# Adafruit_Motor_Bonnet_Rev_A.net
KiCad netlist of a schematic drawn in EAGLE
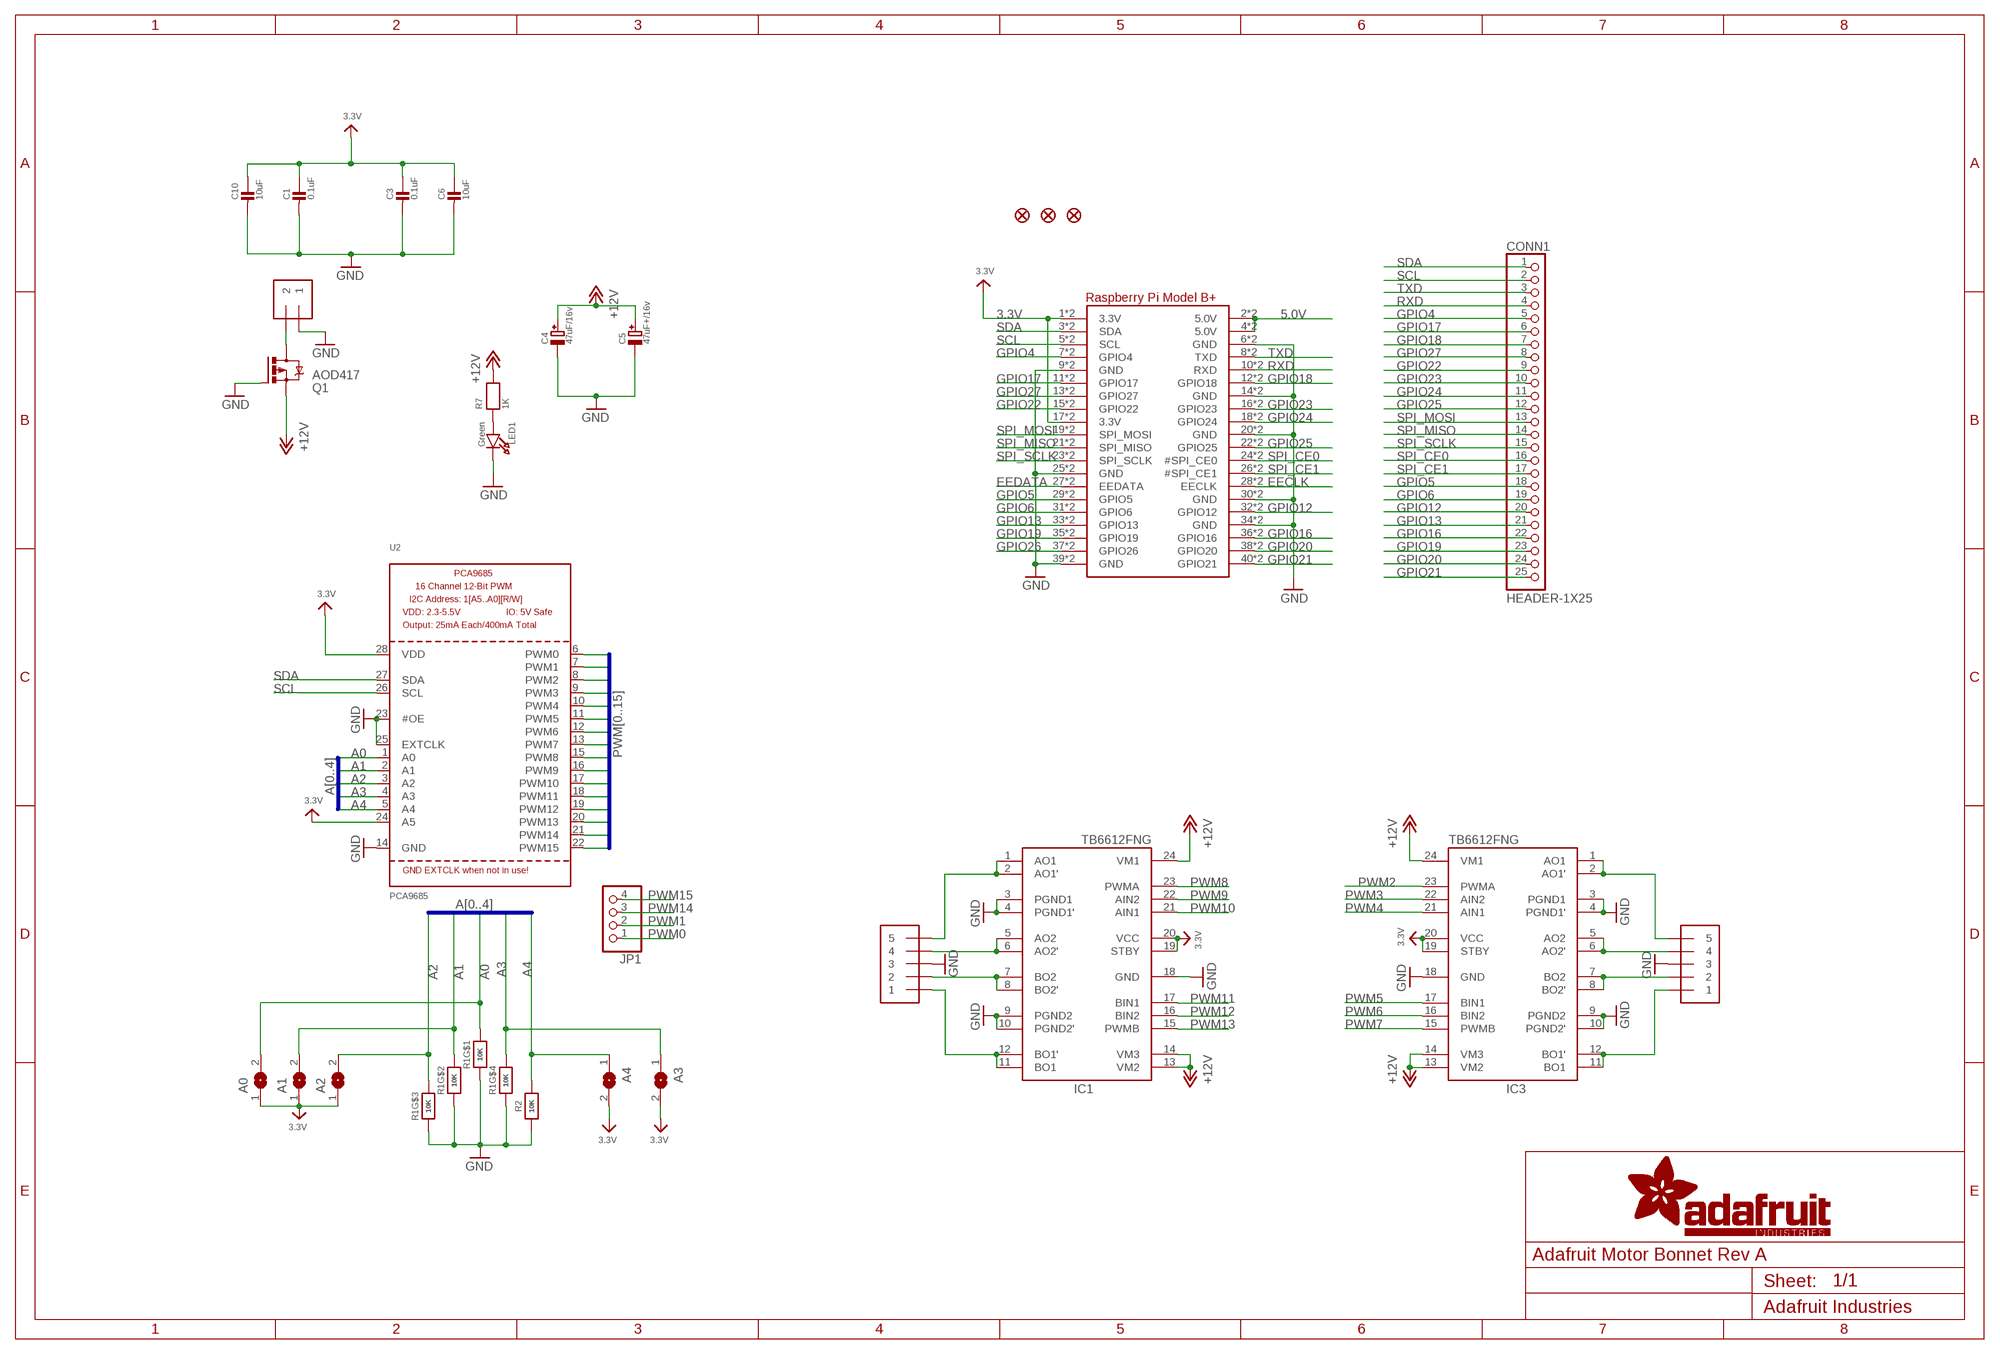
[diagram p0: schematic, sheet 1]

(export (version "E")
  (design (tool "Eeschema 10.0.6"))
  (components
    (comp (ref "A0")
      (value "SOLDERJUMPERREFLOW_NOPASTE")
      (footprint "eagle-import:SOLDERJUMPER_REFLOW_NOPASTE")
      (libsource (lib "eagle-import") (part "SOLDERJUMPERREFLOW_NOPASTE"))
    )
    (comp (ref "A1")
      (value "SOLDERJUMPERREFLOW_NOPASTE")
      (footprint "eagle-import:SOLDERJUMPER_REFLOW_NOPASTE")
      (libsource (lib "eagle-import") (part "SOLDERJUMPERREFLOW_NOPASTE"))
    )
    (comp (ref "A2")
      (value "SOLDERJUMPERREFLOW_NOPASTE")
      (footprint "eagle-import:SOLDERJUMPER_REFLOW_NOPASTE")
      (libsource (lib "eagle-import") (part "SOLDERJUMPERREFLOW_NOPASTE"))
    )
    (comp (ref "A3")
      (value "SOLDERJUMPERREFLOW_NOPASTE")
      (footprint "eagle-import:SOLDERJUMPER_REFLOW_NOPASTE")
      (libsource (lib "eagle-import") (part "SOLDERJUMPERREFLOW_NOPASTE"))
    )
    (comp (ref "A4")
      (value "SOLDERJUMPERREFLOW_NOPASTE")
      (footprint "eagle-import:SOLDERJUMPER_REFLOW_NOPASTE")
      (libsource (lib "eagle-import") (part "SOLDERJUMPERREFLOW_NOPASTE"))
    )
    (comp (ref "C1")
      (value "0.1uF")
      (footprint "eagle-import:0603-NO")
      (libsource (lib "eagle-import") (part "CAP_CERAMIC0603_NO"))
    )
    (comp (ref "C3")
      (value "0.1uF")
      (footprint "eagle-import:0603-NO")
      (libsource (lib "eagle-import") (part "CAP_CERAMIC0603_NO"))
    )
    (comp (ref "C4")
      (value "47uF/16v")
      (footprint "eagle-import:PANASONIC_C")
      (libsource (lib "eagle-import") (part "CAP_ELECTROLYTICPANASONIC_C"))
    )
    (comp (ref "C5")
      (value "47uF+/16v")
      (footprint "eagle-import:PANASONIC_C")
      (libsource (lib "eagle-import") (part "CAP_ELECTROLYTICPANASONIC_C"))
    )
    (comp (ref "C6")
      (value "10uF")
      (footprint "eagle-import:0805-NO")
      (libsource (lib "eagle-import") (part "CAP_CERAMIC0805-NOOUTLINE"))
    )
    (comp (ref "C10")
      (value "10uF")
      (footprint "eagle-import:0805-NO")
      (libsource (lib "eagle-import") (part "CAP_CERAMIC0805-NOOUTLINE"))
    )
    (comp (ref "CONN1")
      (value "HEADER-1X25")
      (footprint "eagle-import:1X25_ROUND_70MIL")
      (libsource (lib "eagle-import") (part "HEADER-1X25"))
    )
    (comp (ref "FID1")
      (value "FIDUCIAL_1MM")
      (footprint "eagle-import:FIDUCIAL_1MM")
      (libsource (lib "eagle-import") (part "FIDUCIAL_1MM"))
    )
    (comp (ref "FID2")
      (value "FIDUCIAL_1MM")
      (footprint "eagle-import:FIDUCIAL_1MM")
      (libsource (lib "eagle-import") (part "FIDUCIAL_1MM"))
    )
    (comp (ref "FID3")
      (value "FIDUCIAL_1MM")
      (footprint "eagle-import:FIDUCIAL_1MM")
      (libsource (lib "eagle-import") (part "FIDUCIAL_1MM"))
    )
    (comp (ref "IC1")
      (value "TB6612FNG")
      (footprint "eagle-import:SSOP24")
      (libsource (lib "eagle-import") (part "TB6612FNG"))
    )
    (comp (ref "IC3")
      (value "TB6612FNG")
      (footprint "eagle-import:SSOP24")
      (libsource (lib "eagle-import") (part "TB6612FNG"))
    )
    (comp (ref "J1")
      (value "1X5")
      (footprint "eagle-import:1X05-3.5MM")
      (libsource (lib "eagle-import") (part "1X5"))
    )
    (comp (ref "J3")
      (value "1X5")
      (footprint "eagle-import:1X05-3.5MM")
      (libsource (lib "eagle-import") (part "1X5"))
    )
    (comp (ref "JP1")
      (value "HEADER-1X4ROUND")
      (footprint "eagle-import:1X04_ROUND")
      (libsource (lib "eagle-import") (part "HEADER-1X4ROUND"))
    )
    (comp (ref "LED1")
      (value "Green")
      (footprint "eagle-import:CHIPLED_0805_NOOUTLINE")
      (libsource (lib "eagle-import") (part "LED0805_NOOUTLINE"))
    )
    (comp (ref "MPOWER")
      (value "1X2-3.5MM")
      (footprint "eagle-import:1X2-3.5MM")
      (libsource (lib "eagle-import") (part "1X2-3.5MM"))
    )
    (comp (ref "Q1")
      (value "AOD417")
      (footprint "eagle-import:D-PAK_TO252AA")
      (libsource (lib "eagle-import") (part "IRF?5305R"))
    )
    (comp (ref "R1")
      (value "10K")
      (footprint "eagle-import:RESPACK_4X0603")
      (libsource (lib "eagle-import") (part "RESISTOR_4PACK"))
    )
    (comp (ref "R2")
      (value "10K")
      (footprint "eagle-import:0603-NO")
      (libsource (lib "eagle-import") (part "RESISTOR_0603_NOOUT"))
    )
    (comp (ref "R7")
      (value "1K")
      (footprint "eagle-import:0603-NO")
      (libsource (lib "eagle-import") (part "RESISTOR_0603_NOOUT"))
    )
    (comp (ref "RPI1")
      (value "RASPBERRYPI_BPLUS_BONNET_THMSMT")
      (footprint "eagle-import:PI_BONNET_THMSMT")
      (libsource (lib "eagle-import") (part "RASPBERRYPI_BPLUS_BONNET_THMSMT"))
    )
    (comp (ref "U2")
      (value "PCA9685")
      (footprint "eagle-import:TSSOP28")
      (libsource (lib "eagle-import") (part "PCA9685"))
    )
  )
  (nets
    (net (code "1") (name "+12V") (class "Default")
      (node (ref "C4") (pin "+") (pinfunction "+_+") (pintype "passive"))
      (node (ref "C5") (pin "+") (pinfunction "+_+") (pintype "passive"))
      (node (ref "IC1") (pin "13") (pinfunction "VM2_13") (pintype "power_in"))
      (node (ref "IC1") (pin "14") (pinfunction "VM3_14") (pintype "power_in"))
      (node (ref "IC1") (pin "24") (pinfunction "VM1_24") (pintype "power_in"))
      (node (ref "IC3") (pin "13") (pinfunction "VM2_13") (pintype "power_in"))
      (node (ref "IC3") (pin "14") (pinfunction "VM3_14") (pintype "power_in"))
      (node (ref "IC3") (pin "24") (pinfunction "VM1_24") (pintype "power_in"))
      (node (ref "Q1") (pin "3") (pinfunction "S_3") (pintype "passive"))
      (node (ref "R7") (pin "2") (pinfunction "2_2") (pintype "passive"))
    )
    (net (code "2") (name "/5.0V") (class "Default")
      (node (ref "RPI1") (pin "2") (pinfunction "5.0V_2") (pintype "power_in"))
      (node (ref "RPI1") (pin "4") (pinfunction "5.0V_4") (pintype "power_in"))
      (node (ref "RPI1") (pin "S2") (pinfunction "5.0V_S2") (pintype "power_in"))
      (node (ref "RPI1") (pin "S4") (pinfunction "5.0V_S4") (pintype "power_in"))
    )
    (net (code "3") (name "/A0") (class "Default")
      (node (ref "A0") (pin "2") (pinfunction "2_2") (pintype "passive"))
      (node (ref "R1") (pin "8") (pinfunction "2_8") (pintype "passive"))
      (node (ref "U2") (pin "1") (pinfunction "A0_1") (pintype "bidirectional"))
    )
    (net (code "4") (name "/A1") (class "Default")
      (node (ref "A1") (pin "2") (pinfunction "2_2") (pintype "passive"))
      (node (ref "R1") (pin "7") (pinfunction "2_7") (pintype "passive"))
      (node (ref "U2") (pin "2") (pinfunction "A1_2") (pintype "bidirectional"))
    )
    (net (code "5") (name "/A2") (class "Default")
      (node (ref "A2") (pin "2") (pinfunction "2_2") (pintype "passive"))
      (node (ref "R1") (pin "6") (pinfunction "2_6") (pintype "passive"))
      (node (ref "U2") (pin "3") (pinfunction "A2_3") (pintype "bidirectional"))
    )
    (net (code "6") (name "/A3") (class "Default")
      (node (ref "A3") (pin "1") (pinfunction "1_1") (pintype "passive"))
      (node (ref "R1") (pin "5") (pinfunction "2_5") (pintype "passive"))
      (node (ref "U2") (pin "4") (pinfunction "A3_4") (pintype "bidirectional"))
    )
    (net (code "7") (name "/A4") (class "Default")
      (node (ref "A4") (pin "1") (pinfunction "1_1") (pintype "passive"))
      (node (ref "R2") (pin "2") (pinfunction "2_2") (pintype "passive"))
      (node (ref "U2") (pin "5") (pinfunction "A4_5") (pintype "bidirectional"))
    )
    (net (code "9") (name "/EECLK") (class "Default")
      (node (ref "RPI1") (pin "28") (pinfunction "EECLK_28") (pintype "bidirectional"))
      (node (ref "RPI1") (pin "S28") (pinfunction "EECLK_S28") (pintype "bidirectional"))
    )
    (net (code "10") (name "/EEDATA") (class "Default")
      (node (ref "RPI1") (pin "27") (pinfunction "EEDATA_27") (pintype "bidirectional"))
      (node (ref "RPI1") (pin "S27") (pinfunction "EEDATA_S27") (pintype "bidirectional"))
    )
    (net (code "11") (name "/GPIO4") (class "Default")
      (node (ref "CONN1") (pin "5") (pinfunction "5_5") (pintype "passive"))
      (node (ref "RPI1") (pin "7") (pinfunction "GPIO4_7") (pintype "bidirectional"))
      (node (ref "RPI1") (pin "S7") (pinfunction "GPIO4_S7") (pintype "bidirectional"))
    )
    (net (code "12") (name "/GPIO5") (class "Default")
      (node (ref "CONN1") (pin "18") (pinfunction "18_18") (pintype "passive"))
      (node (ref "RPI1") (pin "29") (pinfunction "GPIO5_29") (pintype "bidirectional"))
      (node (ref "RPI1") (pin "S29") (pinfunction "GPIO5_S29") (pintype "bidirectional"))
    )
    (net (code "13") (name "/GPIO6") (class "Default")
      (node (ref "CONN1") (pin "19") (pinfunction "19_19") (pintype "passive"))
      (node (ref "RPI1") (pin "31") (pinfunction "GPIO6_31") (pintype "bidirectional"))
      (node (ref "RPI1") (pin "S31") (pinfunction "GPIO6_S31") (pintype "bidirectional"))
    )
    (net (code "14") (name "/GPIO12") (class "Default")
      (node (ref "CONN1") (pin "20") (pinfunction "20_20") (pintype "passive"))
      (node (ref "RPI1") (pin "32") (pinfunction "GPIO12_32") (pintype "bidirectional"))
      (node (ref "RPI1") (pin "S32") (pinfunction "GPIO12_S32") (pintype "bidirectional"))
    )
    (net (code "15") (name "/GPIO13") (class "Default")
      (node (ref "CONN1") (pin "21") (pinfunction "21_21") (pintype "passive"))
      (node (ref "RPI1") (pin "33") (pinfunction "GPIO13_33") (pintype "bidirectional"))
      (node (ref "RPI1") (pin "S33") (pinfunction "GPIO13_S33") (pintype "bidirectional"))
    )
    (net (code "16") (name "/GPIO16") (class "Default")
      (node (ref "CONN1") (pin "22") (pinfunction "22_22") (pintype "passive"))
      (node (ref "RPI1") (pin "36") (pinfunction "GPIO16_36") (pintype "bidirectional"))
      (node (ref "RPI1") (pin "S36") (pinfunction "GPIO16_S36") (pintype "bidirectional"))
    )
    (net (code "17") (name "/GPIO17") (class "Default")
      (node (ref "CONN1") (pin "6") (pinfunction "6_6") (pintype "passive"))
      (node (ref "RPI1") (pin "11") (pinfunction "GPIO17_11") (pintype "bidirectional"))
      (node (ref "RPI1") (pin "S11") (pinfunction "GPIO17_S11") (pintype "bidirectional"))
    )
    (net (code "18") (name "/GPIO18") (class "Default")
      (node (ref "CONN1") (pin "7") (pinfunction "7_7") (pintype "passive"))
      (node (ref "RPI1") (pin "12") (pinfunction "GPIO18_12") (pintype "bidirectional"))
      (node (ref "RPI1") (pin "S12") (pinfunction "GPIO18_S12") (pintype "bidirectional"))
    )
    (net (code "19") (name "/GPIO19") (class "Default")
      (node (ref "CONN1") (pin "23") (pinfunction "23_23") (pintype "passive"))
      (node (ref "RPI1") (pin "35") (pinfunction "GPIO19_35") (pintype "bidirectional"))
      (node (ref "RPI1") (pin "S35") (pinfunction "GPIO19_S35") (pintype "bidirectional"))
    )
    (net (code "20") (name "/GPIO20") (class "Default")
      (node (ref "CONN1") (pin "24") (pinfunction "24_24") (pintype "passive"))
      (node (ref "RPI1") (pin "38") (pinfunction "GPIO20_38") (pintype "bidirectional"))
      (node (ref "RPI1") (pin "S38") (pinfunction "GPIO20_S38") (pintype "bidirectional"))
    )
    (net (code "21") (name "/GPIO21") (class "Default")
      (node (ref "CONN1") (pin "25") (pinfunction "25_25") (pintype "passive"))
      (node (ref "RPI1") (pin "40") (pinfunction "GPIO21_40") (pintype "bidirectional"))
      (node (ref "RPI1") (pin "S40") (pinfunction "GPIO21_S40") (pintype "bidirectional"))
    )
    (net (code "22") (name "/GPIO22") (class "Default")
      (node (ref "CONN1") (pin "9") (pinfunction "9_9") (pintype "passive"))
      (node (ref "RPI1") (pin "15") (pinfunction "GPIO22_15") (pintype "bidirectional"))
      (node (ref "RPI1") (pin "S15") (pinfunction "GPIO22_S15") (pintype "bidirectional"))
    )
    (net (code "23") (name "/GPIO23") (class "Default")
      (node (ref "CONN1") (pin "10") (pinfunction "10_10") (pintype "passive"))
      (node (ref "RPI1") (pin "16") (pinfunction "GPIO23_16") (pintype "bidirectional"))
      (node (ref "RPI1") (pin "S16") (pinfunction "GPIO23_S16") (pintype "bidirectional"))
    )
    (net (code "24") (name "/GPIO24") (class "Default")
      (node (ref "CONN1") (pin "11") (pinfunction "11_11") (pintype "passive"))
      (node (ref "RPI1") (pin "18") (pinfunction "GPIO24_18") (pintype "bidirectional"))
      (node (ref "RPI1") (pin "S18") (pinfunction "GPIO24_S18") (pintype "bidirectional"))
    )
    (net (code "25") (name "/GPIO25") (class "Default")
      (node (ref "CONN1") (pin "12") (pinfunction "12_12") (pintype "passive"))
      (node (ref "RPI1") (pin "22") (pinfunction "GPIO25_22") (pintype "bidirectional"))
      (node (ref "RPI1") (pin "S22") (pinfunction "GPIO25_S22") (pintype "bidirectional"))
    )
    (net (code "26") (name "/GPIO26") (class "Default")
      (node (ref "RPI1") (pin "37") (pinfunction "GPIO26_37") (pintype "bidirectional"))
      (node (ref "RPI1") (pin "S37") (pinfunction "GPIO26_S37") (pintype "bidirectional"))
    )
    (net (code "27") (name "/GPIO27") (class "Default")
      (node (ref "CONN1") (pin "8") (pinfunction "8_8") (pintype "passive"))
      (node (ref "RPI1") (pin "13") (pinfunction "GPIO27_13") (pintype "bidirectional"))
      (node (ref "RPI1") (pin "S13") (pinfunction "GPIO27_S13") (pintype "bidirectional"))
    )
    (net (code "28") (name "/PWM0") (class "Default")
      (node (ref "JP1") (pin "1") (pinfunction "1_1") (pintype "passive"))
      (node (ref "U2") (pin "6") (pinfunction "PWM0_6") (pintype "output"))
    )
    (net (code "29") (name "/PWM1") (class "Default")
      (node (ref "JP1") (pin "2") (pinfunction "2_2") (pintype "passive"))
      (node (ref "U2") (pin "7") (pinfunction "PWM1_7") (pintype "output"))
    )
    (net (code "30") (name "/PWM2") (class "Default")
      (node (ref "IC3") (pin "23") (pinfunction "PWMA_23") (pintype "input"))
      (node (ref "U2") (pin "8") (pinfunction "PWM2_8") (pintype "output"))
    )
    (net (code "31") (name "/PWM3") (class "Default")
      (node (ref "IC3") (pin "22") (pinfunction "AIN2_22") (pintype "input"))
      (node (ref "U2") (pin "9") (pinfunction "PWM3_9") (pintype "output"))
    )
    (net (code "32") (name "/PWM4") (class "Default")
      (node (ref "IC3") (pin "21") (pinfunction "AIN1_21") (pintype "input"))
      (node (ref "U2") (pin "10") (pinfunction "PWM4_10") (pintype "output"))
    )
    (net (code "33") (name "/PWM5") (class "Default")
      (node (ref "IC3") (pin "17") (pinfunction "BIN1_17") (pintype "input"))
      (node (ref "U2") (pin "11") (pinfunction "PWM5_11") (pintype "output"))
    )
    (net (code "34") (name "/PWM6") (class "Default")
      (node (ref "IC3") (pin "16") (pinfunction "BIN2_16") (pintype "input"))
      (node (ref "U2") (pin "12") (pinfunction "PWM6_12") (pintype "output"))
    )
    (net (code "35") (name "/PWM7") (class "Default")
      (node (ref "IC3") (pin "15") (pinfunction "PWMB_15") (pintype "input"))
      (node (ref "U2") (pin "13") (pinfunction "PWM7_13") (pintype "output"))
    )
    (net (code "36") (name "/PWM8") (class "Default")
      (node (ref "IC1") (pin "23") (pinfunction "PWMA_23") (pintype "input"))
      (node (ref "U2") (pin "15") (pinfunction "PWM8_15") (pintype "output"))
    )
    (net (code "37") (name "/PWM9") (class "Default")
      (node (ref "IC1") (pin "22") (pinfunction "AIN2_22") (pintype "input"))
      (node (ref "U2") (pin "16") (pinfunction "PWM9_16") (pintype "output"))
    )
    (net (code "38") (name "/PWM10") (class "Default")
      (node (ref "IC1") (pin "21") (pinfunction "AIN1_21") (pintype "input"))
      (node (ref "U2") (pin "17") (pinfunction "PWM10_17") (pintype "output"))
    )
    (net (code "39") (name "/PWM11") (class "Default")
      (node (ref "IC1") (pin "17") (pinfunction "BIN1_17") (pintype "input"))
      (node (ref "U2") (pin "18") (pinfunction "PWM11_18") (pintype "output"))
    )
    (net (code "40") (name "/PWM12") (class "Default")
      (node (ref "IC1") (pin "16") (pinfunction "BIN2_16") (pintype "input"))
      (node (ref "U2") (pin "19") (pinfunction "PWM12_19") (pintype "output"))
    )
    (net (code "41") (name "/PWM13") (class "Default")
      (node (ref "IC1") (pin "15") (pinfunction "PWMB_15") (pintype "input"))
      (node (ref "U2") (pin "20") (pinfunction "PWM13_20") (pintype "output"))
    )
    (net (code "42") (name "/PWM14") (class "Default")
      (node (ref "JP1") (pin "3") (pinfunction "3_3") (pintype "passive"))
      (node (ref "U2") (pin "21") (pinfunction "PWM14_21") (pintype "output"))
    )
    (net (code "43") (name "/PWM15") (class "Default")
      (node (ref "JP1") (pin "4") (pinfunction "4_4") (pintype "passive"))
      (node (ref "U2") (pin "22") (pinfunction "PWM15_22") (pintype "output"))
    )
    (net (code "45") (name "/RXD") (class "Default")
      (node (ref "CONN1") (pin "4") (pinfunction "4_4") (pintype "passive"))
      (node (ref "RPI1") (pin "10") (pinfunction "RXD_10") (pintype "bidirectional"))
      (node (ref "RPI1") (pin "S10") (pinfunction "RXD_S10") (pintype "bidirectional"))
    )
    (net (code "46") (name "/SCL") (class "Default")
      (node (ref "CONN1") (pin "2") (pinfunction "2_2") (pintype "passive"))
      (node (ref "RPI1") (pin "5") (pinfunction "SCL_5") (pintype "bidirectional"))
      (node (ref "RPI1") (pin "S5") (pinfunction "SCL_S5") (pintype "bidirectional"))
      (node (ref "U2") (pin "26") (pinfunction "SCL_26") (pintype "bidirectional"))
    )
    (net (code "47") (name "/SDA") (class "Default")
      (node (ref "CONN1") (pin "1") (pinfunction "1_1") (pintype "passive"))
      (node (ref "RPI1") (pin "3") (pinfunction "SDA_3") (pintype "bidirectional"))
      (node (ref "RPI1") (pin "S3") (pinfunction "SDA_S3") (pintype "bidirectional"))
      (node (ref "U2") (pin "27") (pinfunction "SDA_27") (pintype "bidirectional"))
    )
    (net (code "48") (name "/SPI_CE0") (class "Default")
      (node (ref "CONN1") (pin "16") (pinfunction "16_16") (pintype "passive"))
      (node (ref "RPI1") (pin "24") (pinfunction "#SPI_CE0_24") (pintype "bidirectional"))
      (node (ref "RPI1") (pin "S24") (pinfunction "#SPI_CE0_S24") (pintype "bidirectional"))
    )
    (net (code "49") (name "/SPI_CE1") (class "Default")
      (node (ref "CONN1") (pin "17") (pinfunction "17_17") (pintype "passive"))
      (node (ref "RPI1") (pin "26") (pinfunction "#SPI_CE1_26") (pintype "bidirectional"))
      (node (ref "RPI1") (pin "S26") (pinfunction "#SPI_CE1_S26") (pintype "bidirectional"))
    )
    (net (code "50") (name "/SPI_MISO") (class "Default")
      (node (ref "CONN1") (pin "14") (pinfunction "14_14") (pintype "passive"))
      (node (ref "RPI1") (pin "21") (pinfunction "SPI_MISO_21") (pintype "bidirectional"))
      (node (ref "RPI1") (pin "S21") (pinfunction "SPI_MISO_S21") (pintype "bidirectional"))
    )
    (net (code "51") (name "/SPI_MOSI") (class "Default")
      (node (ref "CONN1") (pin "13") (pinfunction "13_13") (pintype "passive"))
      (node (ref "RPI1") (pin "19") (pinfunction "SPI_MOSI_19") (pintype "bidirectional"))
      (node (ref "RPI1") (pin "S19") (pinfunction "SPI_MOSI_S19") (pintype "bidirectional"))
    )
    (net (code "52") (name "/SPI_SCLK") (class "Default")
      (node (ref "CONN1") (pin "15") (pinfunction "15_15") (pintype "passive"))
      (node (ref "RPI1") (pin "23") (pinfunction "SPI_SCLK_23") (pintype "bidirectional"))
      (node (ref "RPI1") (pin "S23") (pinfunction "SPI_SCLK_S23") (pintype "bidirectional"))
    )
    (net (code "53") (name "/TXD") (class "Default")
      (node (ref "CONN1") (pin "3") (pinfunction "3_3") (pintype "passive"))
      (node (ref "RPI1") (pin "8") (pinfunction "TXD_8") (pintype "bidirectional"))
      (node (ref "RPI1") (pin "S8") (pinfunction "TXD_S8") (pintype "bidirectional"))
    )
    (net (code "54") (name "3.3V") (class "Default")
      (node (ref "A0") (pin "1") (pinfunction "1_1") (pintype "passive"))
      (node (ref "A1") (pin "1") (pinfunction "1_1") (pintype "passive"))
      (node (ref "A2") (pin "1") (pinfunction "1_1") (pintype "passive"))
      (node (ref "A3") (pin "2") (pinfunction "2_2") (pintype "passive"))
      (node (ref "A4") (pin "2") (pinfunction "2_2") (pintype "passive"))
      (node (ref "C1") (pin "1") (pinfunction "1_1") (pintype "passive"))
      (node (ref "C10") (pin "1") (pinfunction "1_1") (pintype "passive"))
      (node (ref "C3") (pin "1") (pinfunction "1_1") (pintype "passive"))
      (node (ref "C6") (pin "1") (pinfunction "1_1") (pintype "passive"))
      (node (ref "IC1") (pin "19") (pinfunction "STBY_19") (pintype "input"))
      (node (ref "IC1") (pin "20") (pinfunction "VCC_20") (pintype "power_in"))
      (node (ref "IC3") (pin "19") (pinfunction "STBY_19") (pintype "input"))
      (node (ref "IC3") (pin "20") (pinfunction "VCC_20") (pintype "power_in"))
      (node (ref "RPI1") (pin "1") (pinfunction "3.3V_1") (pintype "power_in"))
      (node (ref "RPI1") (pin "17") (pinfunction "3.3V_17") (pintype "power_in"))
      (node (ref "RPI1") (pin "S1") (pinfunction "3.3V_S1") (pintype "power_in"))
      (node (ref "RPI1") (pin "S17") (pinfunction "3.3V_S17") (pintype "power_in"))
      (node (ref "U2") (pin "24") (pinfunction "A5_24") (pintype "bidirectional"))
      (node (ref "U2") (pin "28") (pinfunction "VDD_28") (pintype "power_in"))
    )
    (net (code "55") (name "GND") (class "Default")
      (node (ref "C1") (pin "2") (pinfunction "2_2") (pintype "passive"))
      (node (ref "C10") (pin "2") (pinfunction "2_2") (pintype "passive"))
      (node (ref "C3") (pin "2") (pinfunction "2_2") (pintype "passive"))
      (node (ref "C4") (pin "-") (pinfunction "-_-") (pintype "passive"))
      (node (ref "C5") (pin "-") (pinfunction "-_-") (pintype "passive"))
      (node (ref "C6") (pin "2") (pinfunction "2_2") (pintype "passive"))
      (node (ref "IC1") (pin "10") (pinfunction "PGND2'_10") (pintype "power_in"))
      (node (ref "IC1") (pin "18") (pinfunction "GND_18") (pintype "power_in"))
      (node (ref "IC1") (pin "3") (pinfunction "PGND1_3") (pintype "power_in"))
      (node (ref "IC1") (pin "4") (pinfunction "PGND1'_4") (pintype "power_in"))
      (node (ref "IC1") (pin "9") (pinfunction "PGND2_9") (pintype "power_in"))
      (node (ref "IC3") (pin "10") (pinfunction "PGND2'_10") (pintype "power_in"))
      (node (ref "IC3") (pin "18") (pinfunction "GND_18") (pintype "power_in"))
      (node (ref "IC3") (pin "3") (pinfunction "PGND1_3") (pintype "power_in"))
      (node (ref "IC3") (pin "4") (pinfunction "PGND1'_4") (pintype "power_in"))
      (node (ref "IC3") (pin "9") (pinfunction "PGND2_9") (pintype "power_in"))
      (node (ref "J1") (pin "3") (pinfunction "3_3") (pintype "passive"))
      (node (ref "J3") (pin "3") (pinfunction "3_3") (pintype "passive"))
      (node (ref "LED1") (pin "C") (pinfunction "C_C") (pintype "passive"))
      (node (ref "MPOWER") (pin "1") (pinfunction "1_1") (pintype "passive"))
      (node (ref "Q1") (pin "1") (pinfunction "G_1") (pintype "passive"))
      (node (ref "R1") (pin "1") (pinfunction "1_1") (pintype "passive"))
      (node (ref "R1") (pin "2") (pinfunction "1_2") (pintype "passive"))
      (node (ref "R1") (pin "3") (pinfunction "1_3") (pintype "passive"))
      (node (ref "R1") (pin "4") (pinfunction "1_4") (pintype "passive"))
      (node (ref "R2") (pin "1") (pinfunction "1_1") (pintype "passive"))
      (node (ref "RPI1") (pin "14") (pinfunction "GND_14") (pintype "power_in"))
      (node (ref "RPI1") (pin "20") (pinfunction "GND_20") (pintype "power_in"))
      (node (ref "RPI1") (pin "25") (pinfunction "GND_25") (pintype "power_in"))
      (node (ref "RPI1") (pin "30") (pinfunction "GND_30") (pintype "power_in"))
      (node (ref "RPI1") (pin "34") (pinfunction "GND_34") (pintype "power_in"))
      (node (ref "RPI1") (pin "39") (pinfunction "GND_39") (pintype "power_in"))
      (node (ref "RPI1") (pin "6") (pinfunction "GND_6") (pintype "power_in"))
      (node (ref "RPI1") (pin "9") (pinfunction "GND_9") (pintype "power_in"))
      (node (ref "RPI1") (pin "S14") (pinfunction "GND_S14") (pintype "power_in"))
      (node (ref "RPI1") (pin "S20") (pinfunction "GND_S20") (pintype "power_in"))
      (node (ref "RPI1") (pin "S25") (pinfunction "GND_S25") (pintype "power_in"))
      (node (ref "RPI1") (pin "S30") (pinfunction "GND_S30") (pintype "power_in"))
      (node (ref "RPI1") (pin "S34") (pinfunction "GND_S34") (pintype "power_in"))
      (node (ref "RPI1") (pin "S39") (pinfunction "GND_S39") (pintype "power_in"))
      (node (ref "RPI1") (pin "S6") (pinfunction "GND_S6") (pintype "power_in"))
      (node (ref "RPI1") (pin "S9") (pinfunction "GND_S9") (pintype "power_in"))
      (node (ref "U2") (pin "14") (pinfunction "GND_14") (pintype "power_in"))
      (node (ref "U2") (pin "23") (pinfunction "#OE_23") (pintype "input"))
      (node (ref "U2") (pin "25") (pinfunction "EXTCLK_25") (pintype "input"))
    )
    (net (code "56") (name "Net-(IC1-AO1')") (class "Default")
      (node (ref "IC1") (pin "1") (pinfunction "AO1_1") (pintype "output"))
      (node (ref "IC1") (pin "2") (pinfunction "AO1'_2") (pintype "output"))
      (node (ref "J1") (pin "5") (pinfunction "5_5") (pintype "passive"))
    )
    (net (code "57") (name "Net-(IC1-AO2')") (class "Default")
      (node (ref "IC1") (pin "5") (pinfunction "AO2_5") (pintype "output"))
      (node (ref "IC1") (pin "6") (pinfunction "AO2'_6") (pintype "output"))
      (node (ref "J1") (pin "4") (pinfunction "4_4") (pintype "passive"))
    )
    (net (code "58") (name "Net-(IC1-BO1')") (class "Default")
      (node (ref "IC1") (pin "11") (pinfunction "BO1_11") (pintype "output"))
      (node (ref "IC1") (pin "12") (pinfunction "BO1'_12") (pintype "output"))
      (node (ref "J1") (pin "1") (pinfunction "1_1") (pintype "passive"))
    )
    (net (code "59") (name "Net-(IC1-BO2')") (class "Default")
      (node (ref "IC1") (pin "7") (pinfunction "BO2_7") (pintype "output"))
      (node (ref "IC1") (pin "8") (pinfunction "BO2'_8") (pintype "output"))
      (node (ref "J1") (pin "2") (pinfunction "2_2") (pintype "passive"))
    )
    (net (code "60") (name "Net-(IC3-AO1')") (class "Default")
      (node (ref "IC3") (pin "1") (pinfunction "AO1_1") (pintype "output"))
      (node (ref "IC3") (pin "2") (pinfunction "AO1'_2") (pintype "output"))
      (node (ref "J3") (pin "5") (pinfunction "5_5") (pintype "passive"))
    )
    (net (code "61") (name "Net-(IC3-AO2')") (class "Default")
      (node (ref "IC3") (pin "5") (pinfunction "AO2_5") (pintype "output"))
      (node (ref "IC3") (pin "6") (pinfunction "AO2'_6") (pintype "output"))
      (node (ref "J3") (pin "4") (pinfunction "4_4") (pintype "passive"))
    )
    (net (code "62") (name "Net-(IC3-BO1')") (class "Default")
      (node (ref "IC3") (pin "11") (pinfunction "BO1_11") (pintype "output"))
      (node (ref "IC3") (pin "12") (pinfunction "BO1'_12") (pintype "output"))
      (node (ref "J3") (pin "1") (pinfunction "1_1") (pintype "passive"))
    )
    (net (code "63") (name "Net-(IC3-BO2')") (class "Default")
      (node (ref "IC3") (pin "7") (pinfunction "BO2_7") (pintype "output"))
      (node (ref "IC3") (pin "8") (pinfunction "BO2'_8") (pintype "output"))
      (node (ref "J3") (pin "2") (pinfunction "2_2") (pintype "passive"))
    )
    (net (code "64") (name "Net-(LED1-PadA)") (class "Default")
      (node (ref "LED1") (pin "A") (pinfunction "A_A") (pintype "passive"))
      (node (ref "R7") (pin "1") (pinfunction "1_1") (pintype "passive"))
    )
    (net (code "65") (name "Net-(Q1-D)") (class "Default")
      (node (ref "MPOWER") (pin "2") (pinfunction "2_2") (pintype "passive"))
      (node (ref "Q1") (pin "4") (pinfunction "D_4") (pintype "passive"))
    )
  )
)
